# SCH_charge.net
KiCad netlist of a schematic drawn in EasyEDA
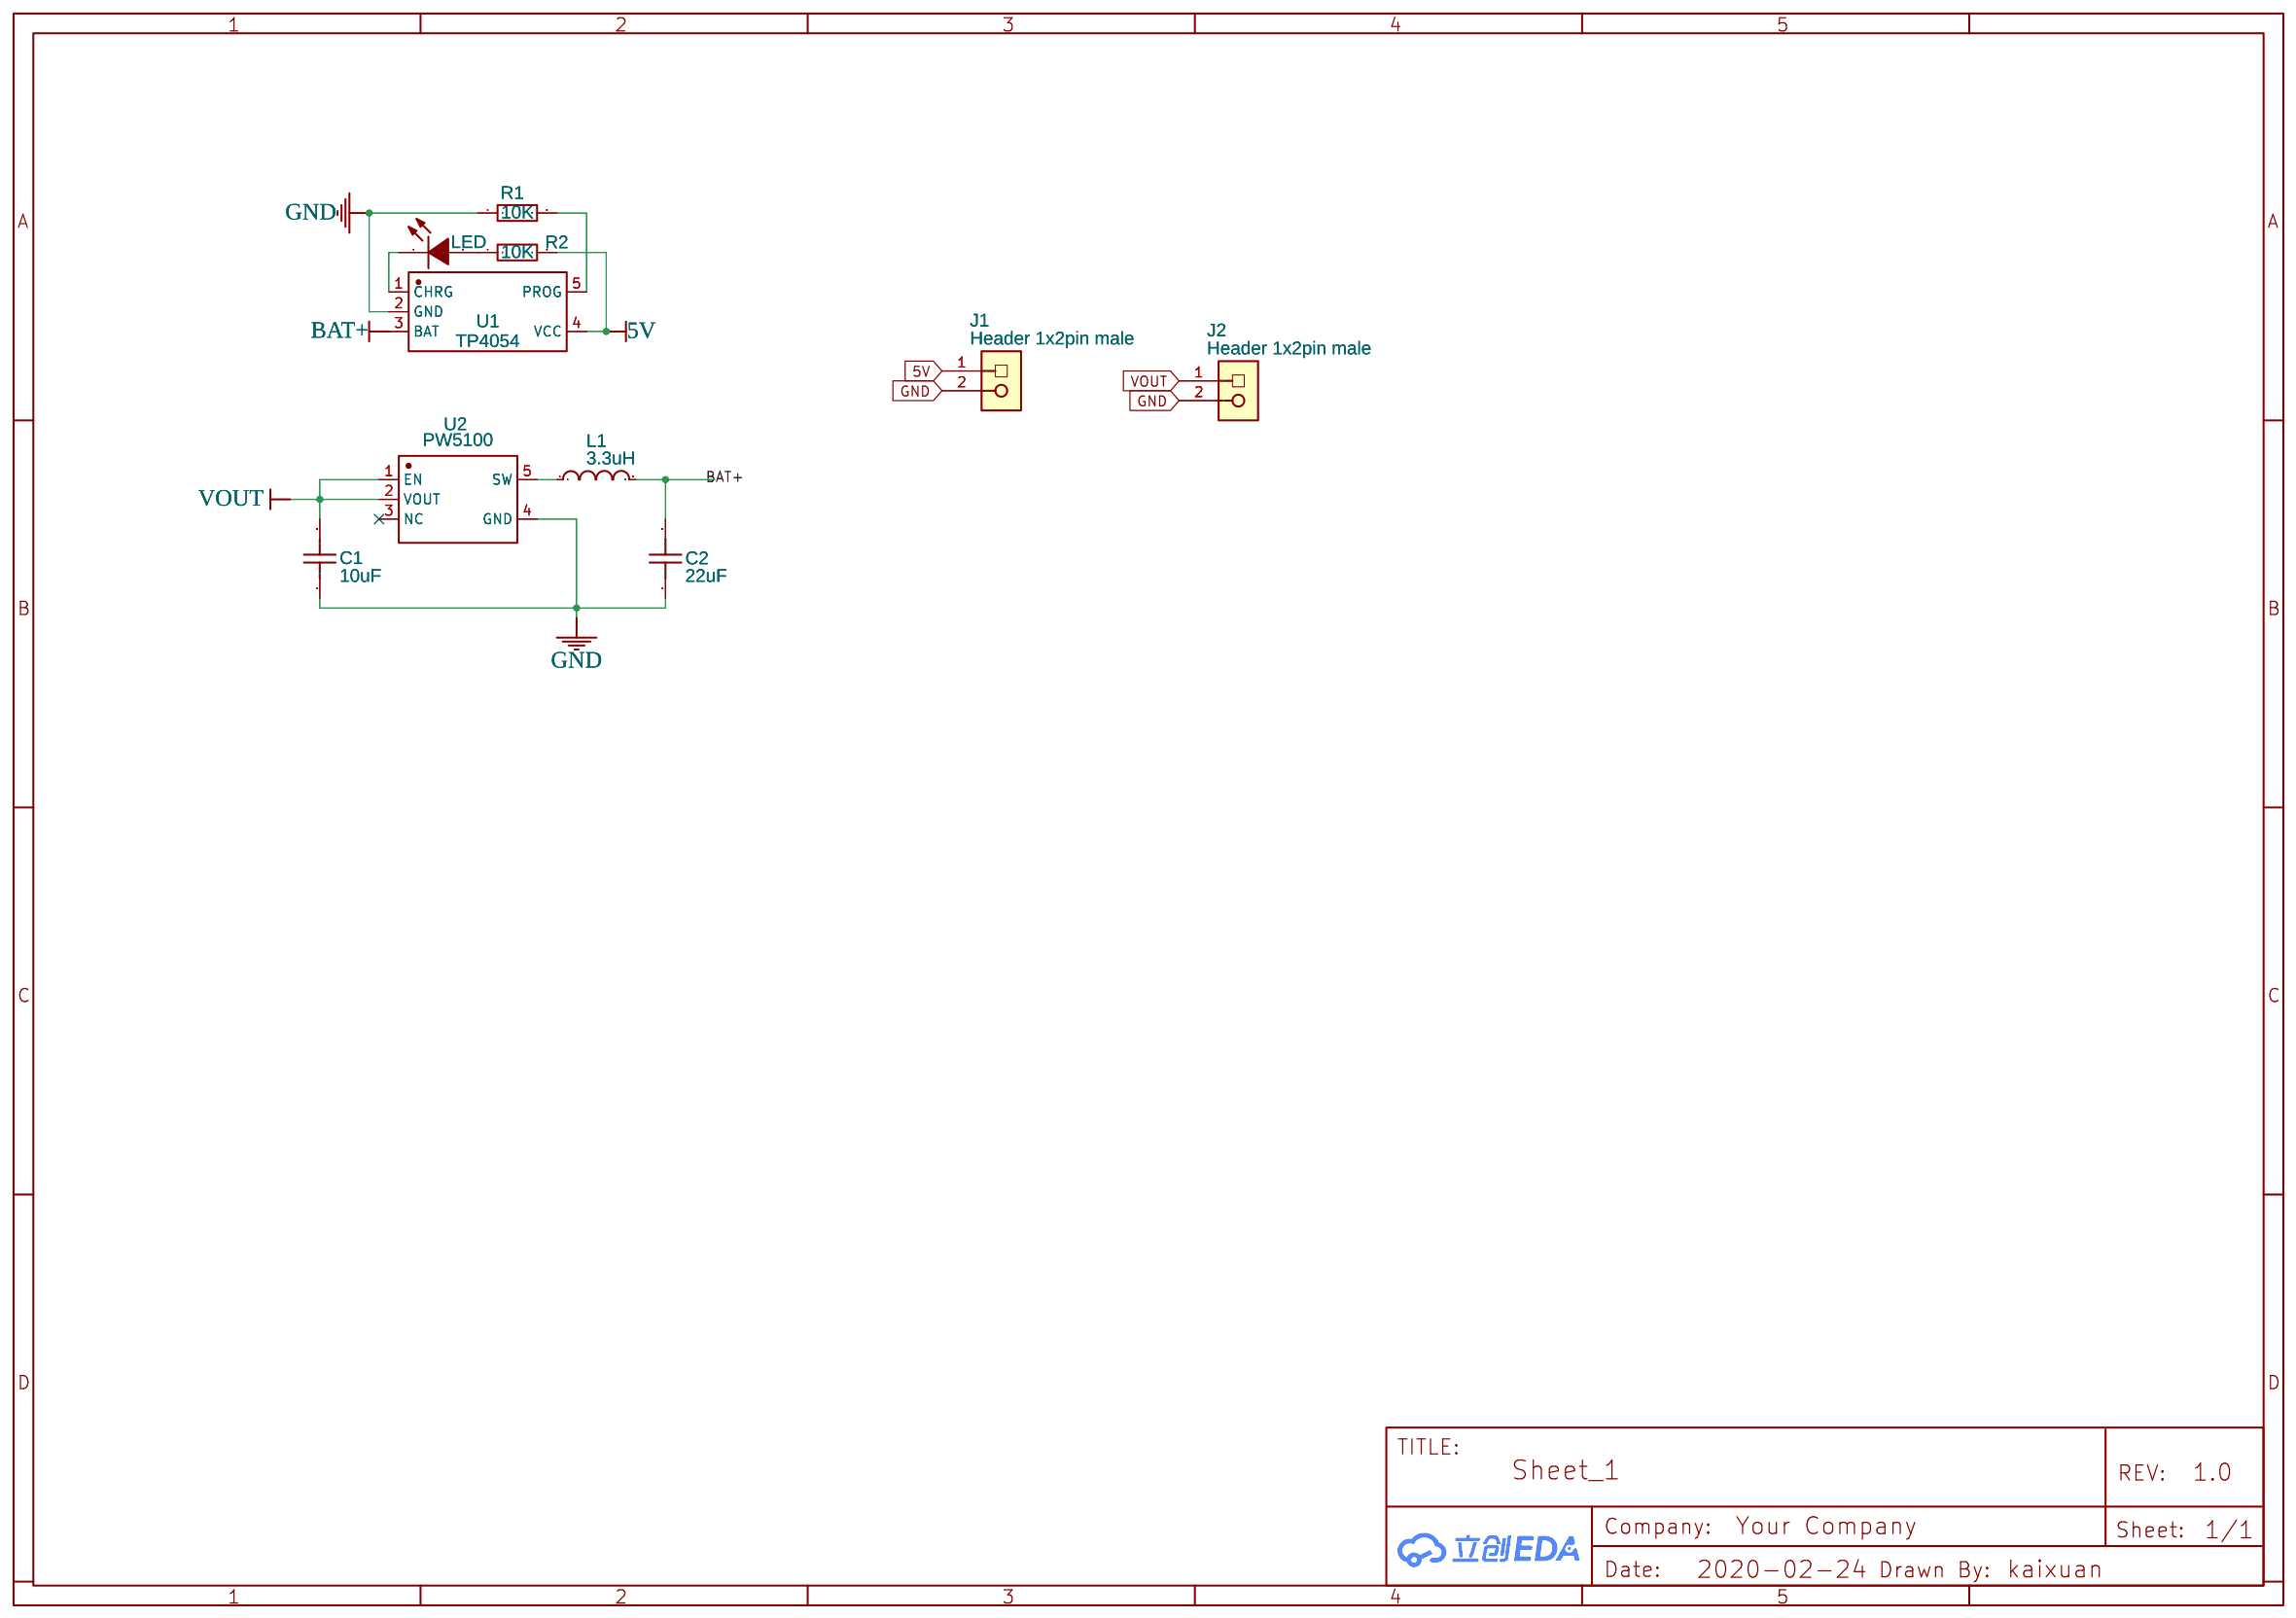
[diagram p0: schematic sheet]

(export (version "E")
  (design (tool "Eeschema 10.0.6"))
  (components
    (comp (ref "C1")
      (value "10uF")
      (fields
        (field (name "BOM_Manufacturer Part") "CL10A106MA8NRNC")
        (field (name "BOM_Supplier Part") "C96446")
      )
      (libsource (lib "") (part "CL10A106MA8NRNC"))
    )
    (comp (ref "C2")
      (value "22uF")
      (fields
        (field (name "BOM_Manufacturer Part") "CL10A226MQ8NRNC")
        (field (name "BOM_Supplier Part") "C59461")
      )
      (libsource (lib "") (part "CL10A226MQ8NRNC"))
    )
    (comp (ref "J1") (value "Header 1x2pin male") (libsource (lib "") (part "Header 1x2pin male")))
    (comp (ref "J2") (value "Header 1x2pin male") (libsource (lib "") (part "Header 1x2pin male")))
    (comp (ref "L1")
      (value "3.3uH")
      (fields
        (field (name "BOM_Manufacturer Part") "LVF252A12-3R3M-N")
        (field (name "BOM_Supplier Part") "C142155")
      )
      (libsource (lib "") (part "LVF252A12-3R3M-N"))
    )
    (comp (ref "LED1")
      (value "LED")
      (fields
        (field (name "BOM_Manufacturer Part") "FC-F1005UGK-520M5")
        (field (name "BOM_Supplier Part") "C130723")
      )
      (libsource (lib "") (part "FC-F1005UGK-520M5"))
    )
    (comp (ref "R1")
      (value "10K")
      (fields
        (field (name "BOM_Manufacturer Part") "RC0402FR-0710KL")
        (field (name "BOM_Supplier Part") "C25744")
      )
      (libsource (lib "") (part "RC0402FR-0710KL"))
    )
    (comp (ref "R2")
      (value "10K")
      (fields
        (field (name "BOM_Manufacturer Part") "RC0402FR-0710KL")
        (field (name "BOM_Supplier Part") "C25744")
      )
      (libsource (lib "") (part "RC0402FR-0710KL"))
    )
    (comp (ref "U1")
      (value "TP4054")
      (fields (field (name "BOM_Supplier Part") "C32574"))
      (libsource (lib "") (part "TP4054"))
    )
    (comp (ref "U2") (value "PW5100") (libsource (lib "") (part "PW5100")))
  )
  (nets
    (net (code "1") (name "5V") (class "Default")
      (node (ref "J1") (pin "1") (pinfunction "1_1") (pintype "unspecified"))
      (node (ref "R2") (pin "2") (pinfunction "2_2") (pintype "input"))
      (node (ref "U1") (pin "4") (pinfunction "VCC_4") (pintype "unspecified"))
    )
    (net (code "2") (name "BAT+") (class "Default")
      (node (ref "C2") (pin "2") (pinfunction "2_2") (pintype "unspecified"))
      (node (ref "L1") (pin "2") (pinfunction "2_2") (pintype "unspecified"))
      (node (ref "U1") (pin "3") (pinfunction "BAT_3") (pintype "unspecified"))
    )
    (net (code "3") (name "GND") (class "Default")
      (node (ref "C1") (pin "1") (pinfunction "1_1") (pintype "unspecified"))
      (node (ref "C2") (pin "1") (pinfunction "1_1") (pintype "unspecified"))
      (node (ref "J1") (pin "2") (pinfunction "2_2") (pintype "unspecified"))
      (node (ref "J2") (pin "2") (pinfunction "2_2") (pintype "unspecified"))
      (node (ref "R1") (pin "1") (pinfunction "1_1") (pintype "input"))
      (node (ref "U1") (pin "2") (pinfunction "GND_2") (pintype "unspecified"))
      (node (ref "U2") (pin "4") (pinfunction "GND_4") (pintype "unspecified"))
    )
    (net (code "4") (name "Net-(LED1-A)") (class "Default")
      (node (ref "LED1") (pin "2") (pinfunction "A_2") (pintype "unspecified"))
      (node (ref "R2") (pin "1") (pinfunction "1_1") (pintype "input"))
    )
    (net (code "5") (name "Net-(LED1-K)") (class "Default")
      (node (ref "LED1") (pin "1") (pinfunction "K_1") (pintype "unspecified"))
      (node (ref "U1") (pin "1") (pinfunction "CHRG_1") (pintype "unspecified"))
    )
    (net (code "6") (name "Net-(U1-PROG)") (class "Default")
      (node (ref "R1") (pin "2") (pinfunction "2_2") (pintype "input"))
      (node (ref "U1") (pin "5") (pinfunction "PROG_5") (pintype "unspecified"))
    )
    (net (code "7") (name "Net-(U2-SW)") (class "Default")
      (node (ref "L1") (pin "1") (pinfunction "1_1") (pintype "unspecified"))
      (node (ref "U2") (pin "5") (pinfunction "SW_5") (pintype "unspecified"))
    )
    (net (code "8") (name "VOUT") (class "Default")
      (node (ref "C1") (pin "2") (pinfunction "2_2") (pintype "unspecified"))
      (node (ref "J2") (pin "1") (pinfunction "1_1") (pintype "unspecified"))
      (node (ref "U2") (pin "1") (pinfunction "EN_1") (pintype "unspecified"))
      (node (ref "U2") (pin "2") (pinfunction "VOUT_2") (pintype "unspecified"))
    )
    (net (code "9") (name "unconnected-(U2-NC-Pad3)") (class "Default")
      (node (ref "U2") (pin "3") (pinfunction "NC_3") (pintype "unspecified+no_connect"))
    )
  )
)
